# design.net
KiCad netlist of a schematic drawn in EasyEDA Pro
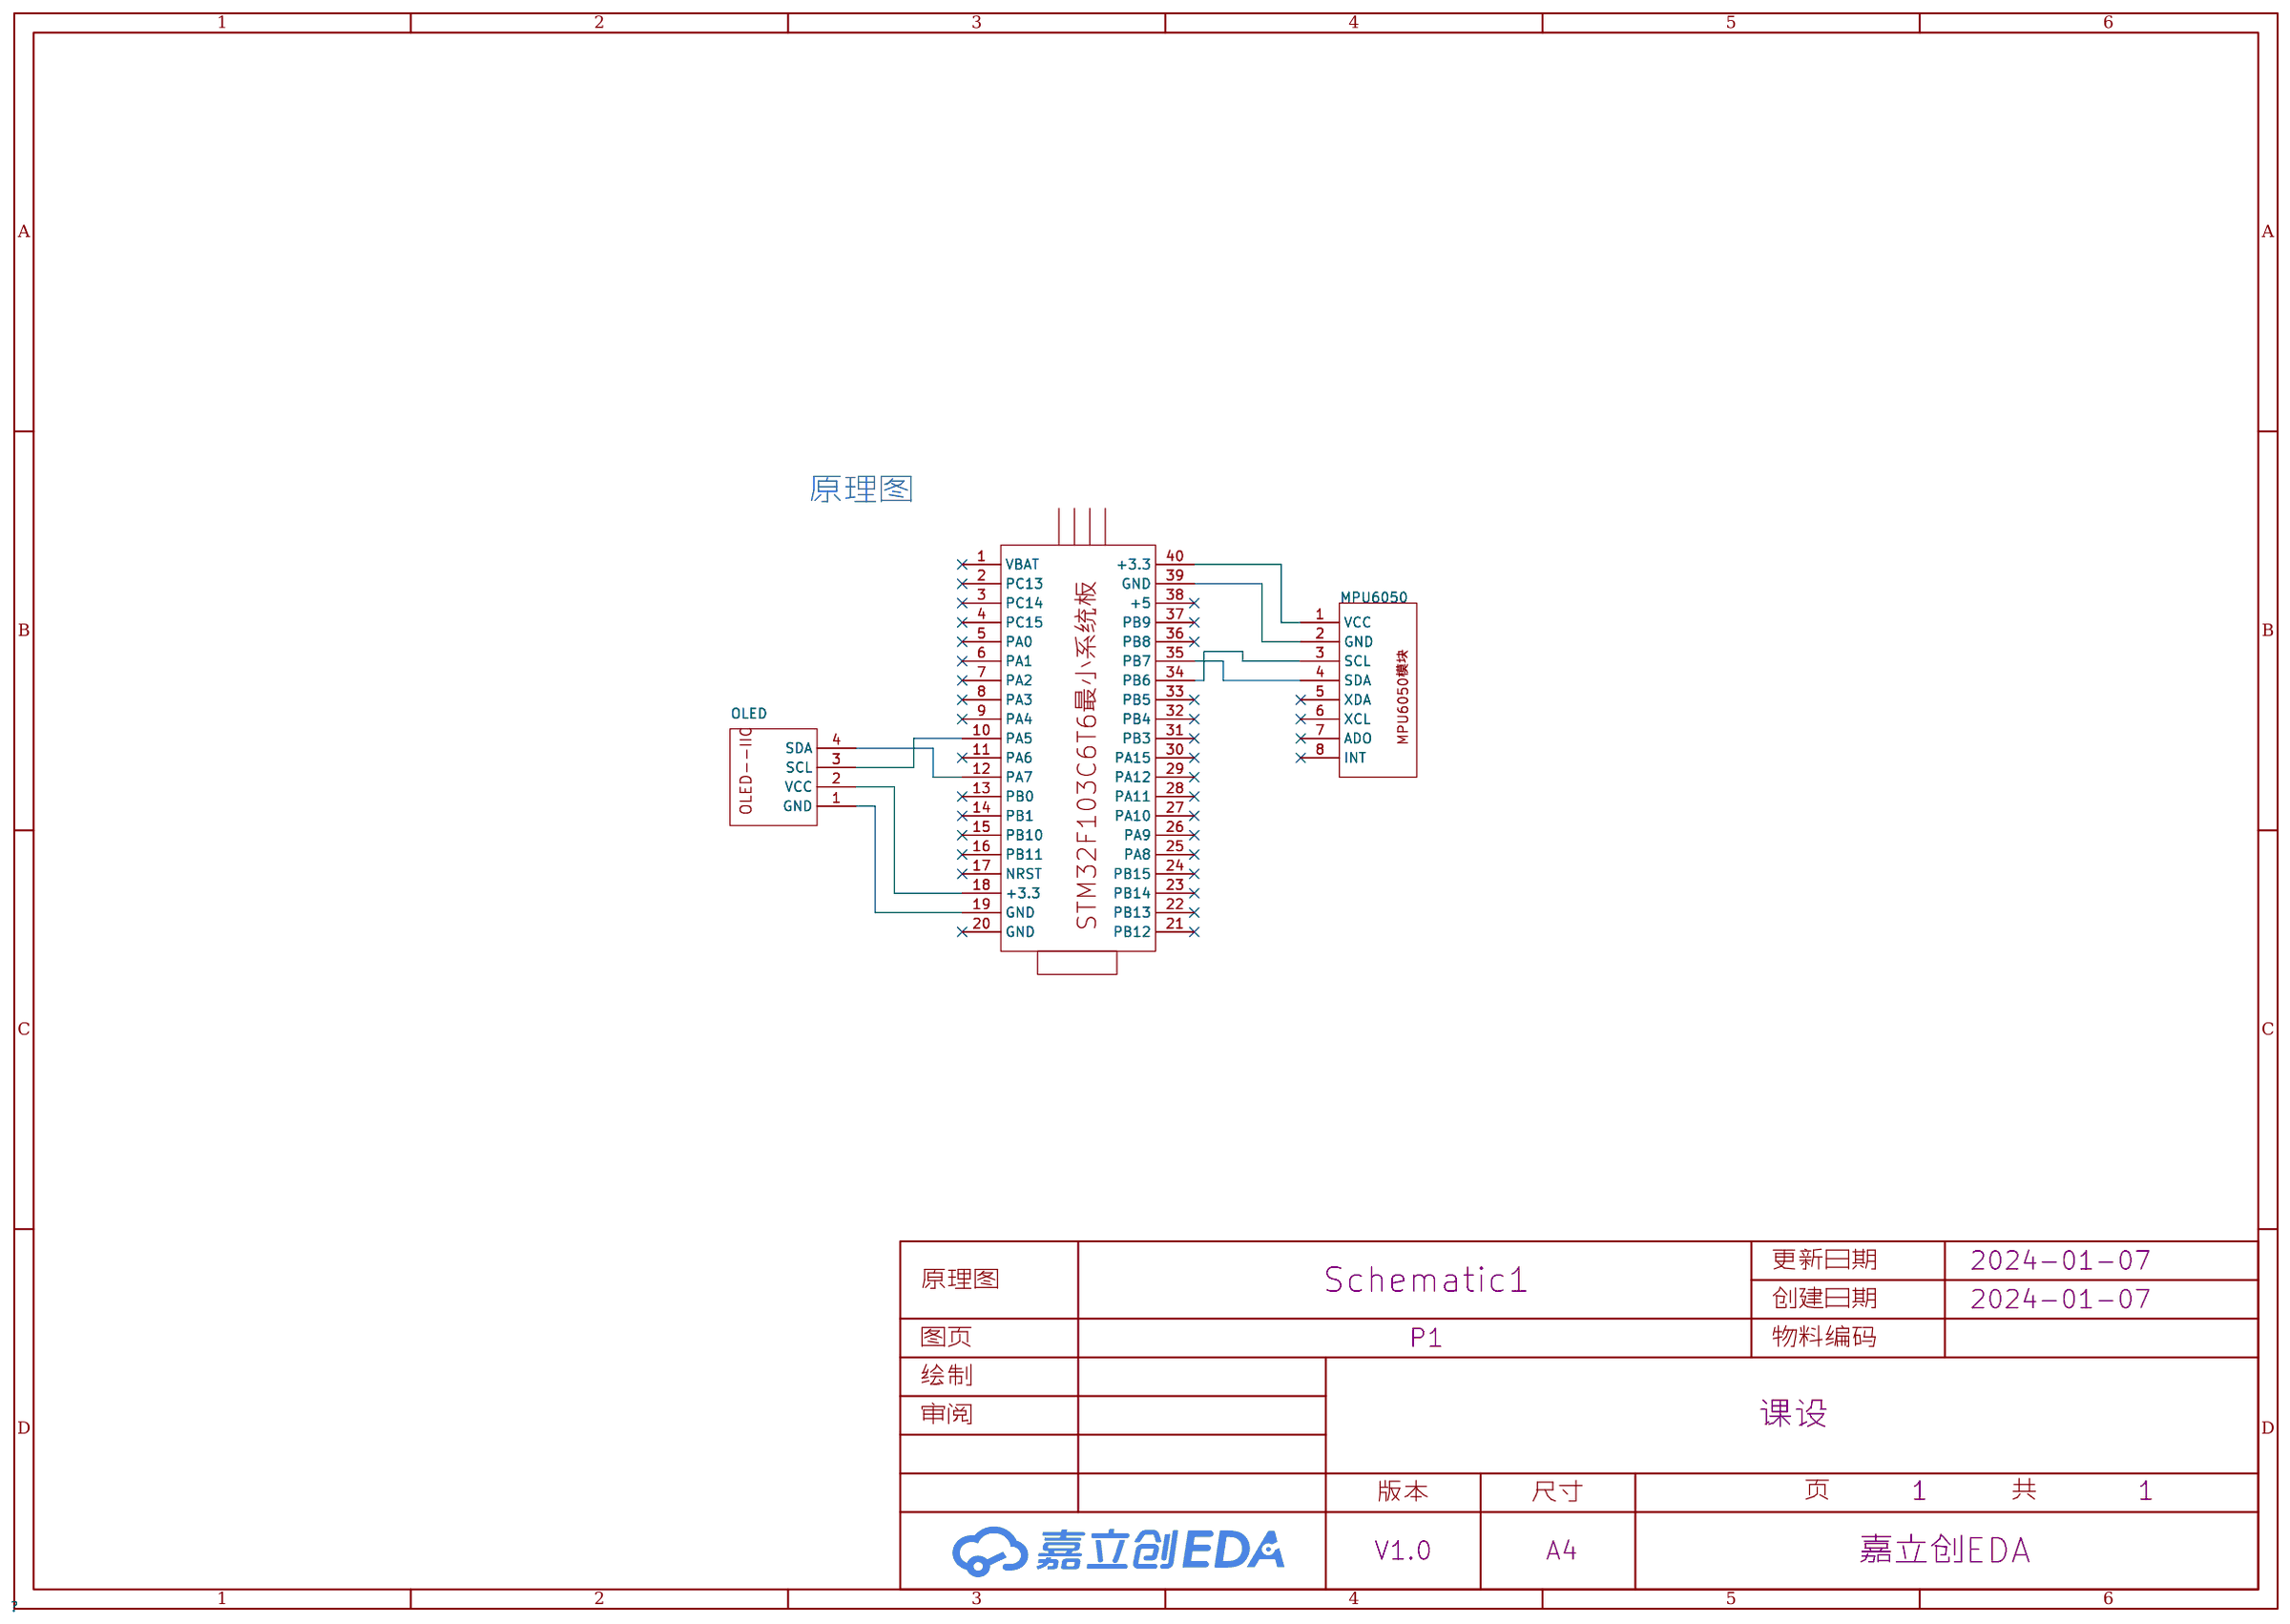
[diagram p0: schematic sheet]

(export (version "E")
  (design (tool "Eeschema 10.0.6"))
  (components
    (comp (ref "MPU6050")
      (value "~")
      (footprint "easyedapro:MPU6050模块")
      (libsource (lib "easyedapro") (part "MPU6050模块"))
    )
    (comp (ref "OLED")
      (value "0.96OLED_4P")
      (footprint "easyedapro:0.96OLED_4P")
      (libsource (lib "easyedapro") (part "0.96OLED_4P_MODULE_JX"))
    )
    (comp (ref "U1")
      (value "~")
      (footprint "easyedapro:STM32F103C8T6最小系统板")
      (libsource (lib "easyedapro") (part "STM32F103C6T6"))
    )
  )
  (nets
    (net (code "1") (name "Net-(MPU6050-GND)") (class "Default")
      (node (ref "MPU6050") (pin "2") (pinfunction "GND_2") (pintype "input"))
      (node (ref "U1") (pin "39") (pinfunction "GND_39") (pintype "input"))
    )
    (net (code "2") (name "Net-(MPU6050-SCL)") (class "Default")
      (node (ref "MPU6050") (pin "3") (pinfunction "SCL_3") (pintype "input"))
      (node (ref "U1") (pin "34") (pinfunction "PB6_34") (pintype "input"))
    )
    (net (code "3") (name "Net-(MPU6050-SDA)") (class "Default")
      (node (ref "MPU6050") (pin "4") (pinfunction "SDA_4") (pintype "input"))
      (node (ref "U1") (pin "35") (pinfunction "PB7_35") (pintype "input"))
    )
    (net (code "4") (name "Net-(MPU6050-VCC)") (class "Default")
      (node (ref "MPU6050") (pin "1") (pinfunction "VCC_1") (pintype "input"))
      (node (ref "U1") (pin "40") (pinfunction "+3.3_40") (pintype "input"))
    )
    (net (code "5") (name "Net-(OLED-GND)") (class "Default")
      (node (ref "OLED") (pin "1") (pinfunction "GND_1") (pintype "input"))
      (node (ref "U1") (pin "19") (pinfunction "GND_19") (pintype "input"))
    )
    (net (code "6") (name "Net-(OLED-SCL)") (class "Default")
      (node (ref "OLED") (pin "3") (pinfunction "SCL_3") (pintype "input"))
      (node (ref "U1") (pin "10") (pinfunction "PA5_10") (pintype "input"))
    )
    (net (code "7") (name "Net-(OLED-SDA)") (class "Default")
      (node (ref "OLED") (pin "4") (pinfunction "SDA_4") (pintype "input"))
      (node (ref "U1") (pin "12") (pinfunction "PA7_12") (pintype "input"))
    )
    (net (code "8") (name "Net-(OLED-VCC)") (class "Default")
      (node (ref "OLED") (pin "2") (pinfunction "VCC_2") (pintype "input"))
      (node (ref "U1") (pin "18") (pinfunction "+3.3_18") (pintype "input"))
    )
    (net (code "9") (name "unconnected-(MPU6050-ADO-Pad7)") (class "Default")
      (node (ref "MPU6050") (pin "7") (pinfunction "ADO_7") (pintype "input+no_connect"))
    )
    (net (code "10") (name "unconnected-(MPU6050-INT-Pad8)") (class "Default")
      (node (ref "MPU6050") (pin "8") (pinfunction "INT_8") (pintype "input+no_connect"))
    )
    (net (code "11") (name "unconnected-(MPU6050-XCL-Pad6)") (class "Default")
      (node (ref "MPU6050") (pin "6") (pinfunction "XCL_6") (pintype "input+no_connect"))
    )
    (net (code "12") (name "unconnected-(MPU6050-XDA-Pad5)") (class "Default")
      (node (ref "MPU6050") (pin "5") (pinfunction "XDA_5") (pintype "input+no_connect"))
    )
    (net (code "13") (name "unconnected-(U1-+5-Pad38)") (class "Default")
      (node (ref "U1") (pin "38") (pinfunction "+5_38") (pintype "input+no_connect"))
    )
    (net (code "14") (name "unconnected-(U1-GND-Pad20)") (class "Default")
      (node (ref "U1") (pin "20") (pinfunction "GND_20") (pintype "input+no_connect"))
    )
    (net (code "15") (name "unconnected-(U1-NRST-Pad17)") (class "Default")
      (node (ref "U1") (pin "17") (pinfunction "NRST_17") (pintype "input+no_connect"))
    )
    (net (code "16") (name "unconnected-(U1-PA0-Pad5)") (class "Default")
      (node (ref "U1") (pin "5") (pinfunction "PA0_5") (pintype "input+no_connect"))
    )
    (net (code "17") (name "unconnected-(U1-PA1-Pad6)") (class "Default")
      (node (ref "U1") (pin "6") (pinfunction "PA1_6") (pintype "input+no_connect"))
    )
    (net (code "18") (name "unconnected-(U1-PA2-Pad7)") (class "Default")
      (node (ref "U1") (pin "7") (pinfunction "PA2_7") (pintype "input+no_connect"))
    )
    (net (code "19") (name "unconnected-(U1-PA3-Pad8)") (class "Default")
      (node (ref "U1") (pin "8") (pinfunction "PA3_8") (pintype "input+no_connect"))
    )
    (net (code "20") (name "unconnected-(U1-PA4-Pad9)") (class "Default")
      (node (ref "U1") (pin "9") (pinfunction "PA4_9") (pintype "input+no_connect"))
    )
    (net (code "21") (name "unconnected-(U1-PA6-Pad11)") (class "Default")
      (node (ref "U1") (pin "11") (pinfunction "PA6_11") (pintype "input+no_connect"))
    )
    (net (code "22") (name "unconnected-(U1-PA8-Pad25)") (class "Default")
      (node (ref "U1") (pin "25") (pinfunction "PA8_25") (pintype "input+no_connect"))
    )
    (net (code "23") (name "unconnected-(U1-PA9-Pad26)") (class "Default")
      (node (ref "U1") (pin "26") (pinfunction "PA9_26") (pintype "input+no_connect"))
    )
    (net (code "24") (name "unconnected-(U1-PA10-Pad27)") (class "Default")
      (node (ref "U1") (pin "27") (pinfunction "PA10_27") (pintype "input+no_connect"))
    )
    (net (code "25") (name "unconnected-(U1-PA11-Pad28)") (class "Default")
      (node (ref "U1") (pin "28") (pinfunction "PA11_28") (pintype "input+no_connect"))
    )
    (net (code "26") (name "unconnected-(U1-PA12-Pad29)") (class "Default")
      (node (ref "U1") (pin "29") (pinfunction "PA12_29") (pintype "input+no_connect"))
    )
    (net (code "27") (name "unconnected-(U1-PA15-Pad30)") (class "Default")
      (node (ref "U1") (pin "30") (pinfunction "PA15_30") (pintype "input+no_connect"))
    )
    (net (code "28") (name "unconnected-(U1-PB0-Pad13)") (class "Default")
      (node (ref "U1") (pin "13") (pinfunction "PB0_13") (pintype "input+no_connect"))
    )
    (net (code "29") (name "unconnected-(U1-PB1-Pad14)") (class "Default")
      (node (ref "U1") (pin "14") (pinfunction "PB1_14") (pintype "input+no_connect"))
    )
    (net (code "30") (name "unconnected-(U1-PB3-Pad31)") (class "Default")
      (node (ref "U1") (pin "31") (pinfunction "PB3_31") (pintype "input+no_connect"))
    )
    (net (code "31") (name "unconnected-(U1-PB4-Pad32)") (class "Default")
      (node (ref "U1") (pin "32") (pinfunction "PB4_32") (pintype "input+no_connect"))
    )
    (net (code "32") (name "unconnected-(U1-PB5-Pad33)") (class "Default")
      (node (ref "U1") (pin "33") (pinfunction "PB5_33") (pintype "input+no_connect"))
    )
    (net (code "33") (name "unconnected-(U1-PB8-Pad36)") (class "Default")
      (node (ref "U1") (pin "36") (pinfunction "PB8_36") (pintype "input+no_connect"))
    )
    (net (code "34") (name "unconnected-(U1-PB9-Pad37)") (class "Default")
      (node (ref "U1") (pin "37") (pinfunction "PB9_37") (pintype "input+no_connect"))
    )
    (net (code "35") (name "unconnected-(U1-PB10-Pad15)") (class "Default")
      (node (ref "U1") (pin "15") (pinfunction "PB10_15") (pintype "input+no_connect"))
    )
    (net (code "36") (name "unconnected-(U1-PB11-Pad16)") (class "Default")
      (node (ref "U1") (pin "16") (pinfunction "PB11_16") (pintype "input+no_connect"))
    )
    (net (code "37") (name "unconnected-(U1-PB12-Pad21)") (class "Default")
      (node (ref "U1") (pin "21") (pinfunction "PB12_21") (pintype "input+no_connect"))
    )
    (net (code "38") (name "unconnected-(U1-PB13-Pad22)") (class "Default")
      (node (ref "U1") (pin "22") (pinfunction "PB13_22") (pintype "input+no_connect"))
    )
    (net (code "39") (name "unconnected-(U1-PB14-Pad23)") (class "Default")
      (node (ref "U1") (pin "23") (pinfunction "PB14_23") (pintype "input+no_connect"))
    )
    (net (code "40") (name "unconnected-(U1-PB15-Pad24)") (class "Default")
      (node (ref "U1") (pin "24") (pinfunction "PB15_24") (pintype "input+no_connect"))
    )
    (net (code "41") (name "unconnected-(U1-PC13-Pad2)") (class "Default")
      (node (ref "U1") (pin "2") (pinfunction "PC13_2") (pintype "input+no_connect"))
    )
    (net (code "42") (name "unconnected-(U1-PC14-Pad3)") (class "Default")
      (node (ref "U1") (pin "3") (pinfunction "PC14_3") (pintype "input+no_connect"))
    )
    (net (code "43") (name "unconnected-(U1-PC15-Pad4)") (class "Default")
      (node (ref "U1") (pin "4") (pinfunction "PC15_4") (pintype "input+no_connect"))
    )
    (net (code "44") (name "unconnected-(U1-VBAT-Pad1)") (class "Default")
      (node (ref "U1") (pin "1") (pinfunction "VBAT_1") (pintype "input+no_connect"))
    )
  )
)
